# Power_981228.net
KiCad netlist of a schematic drawn in Altium Designer
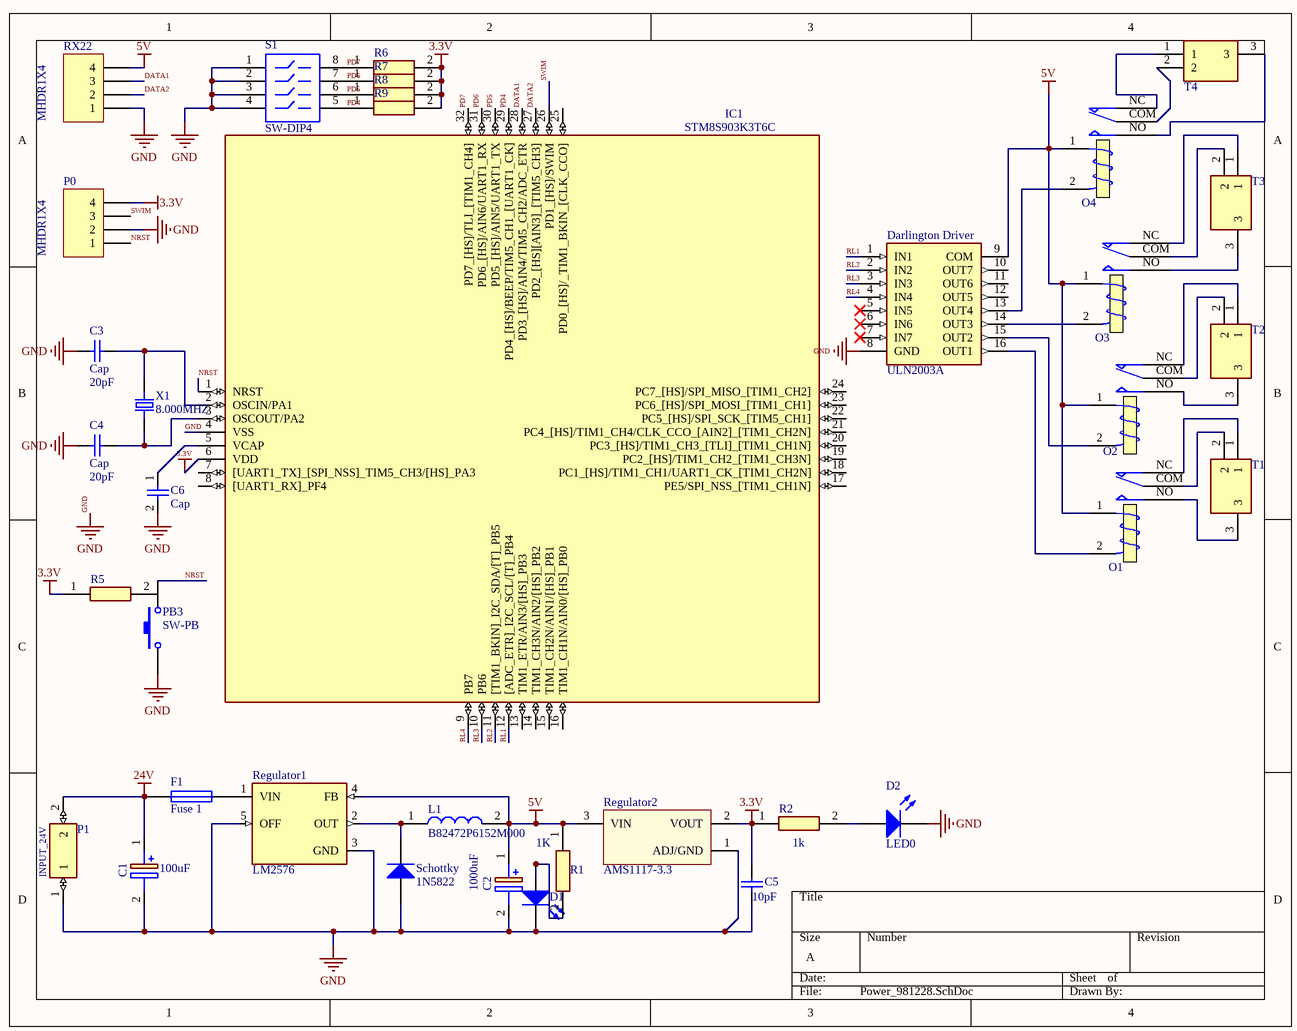
[diagram p0: Power_981228.SchDoc]

(export (version "E")
  (design (tool "Eeschema 10.0.6"))
  (components
    (comp (ref "C1")
      (value "100uF")
      (footprint "SamacSys:CAPPRD550W60D1050H2150")
      (description "Capacitor Polarised")
      (fields (field (name "MANUFACTURER_PART_NUMBER") "108CKE025M"))
      (libsource (lib "*") (part "108CKE025M"))
    )
    (comp (ref "C2")
      (value "1000uF")
      (footprint "SamacSys:CAPPRD550W60D1050H2150")
      (description "Capacitor Polarised")
      (fields (field (name "MANUFACTURER_PART_NUMBER") "108CKE025M"))
      (libsource (lib "*") (part "108CKE025M"))
    )
    (comp (ref "C3")
      (value "Cap")
      (footprint "RAD-0.3")
      (description "Capacitor")
      (fields (field (name "ALTIUM_VALUE") "20pF") (field (name "PUBLISHER") "Altium Limited"))
      (libsource (lib "Miscellaneous Devices") (part "Cap"))
    )
    (comp (ref "C4")
      (value "Cap")
      (footprint "RAD-0.3")
      (description "Capacitor")
      (fields (field (name "ALTIUM_VALUE") "20pF") (field (name "PUBLISHER") "Altium Limited"))
      (libsource (lib "Miscellaneous Devices") (part "Cap"))
    )
    (comp (ref "C5")
      (value "10pF")
      (footprint "RAD-0.3")
      (description "Capacitor")
      (fields (field (name "Comment") "Cap") (field (name "PUBLISHER") "Altium Limited"))
      (libsource (lib "Miscellaneous Devices") (part "Cap"))
    )
    (comp (ref "C6")
      (value "Cap")
      (footprint "RAD-0.3")
      (description "Capacitor")
      (fields (field (name "PUBLISHER") "Altium Limited"))
      (libsource (lib "") (part "Cap_1"))
    )
    (comp (ref "D1")
      (value "LED0")
      (footprint "LED-0")
      (description "Typical INFRARED GaAs LED")
      (fields (field (name "PUBLISHER") "Altium Limited"))
      (libsource (lib "Miscellaneous Devices") (part "LED0"))
    )
    (comp (ref "D2")
      (value "LED0")
      (footprint "LED-0")
      (description "Typical INFRARED GaAs LED")
      (fields (field (name "PUBLISHER") "Altium Limited"))
      (libsource (lib "Miscellaneous Devices") (part "LED0"))
    )
    (comp (ref "Darlington Driver")
      (value "ULN2003A")
      (footprint "SamacSys:DIP794W56P254L1918H533Q16N")
      (description "Integrated Circuit")
      (fields (field (name "MOUSER PART NUMBER") "511-ULN2003A") (field (name "RS PART NUMBER") "6868209"))
      (libsource (lib "*") (part "ULN2003A"))
    )
    (comp (ref "F1")
      (value "Fuse 1")
      (footprint "PIN-W2/E2.8")
      (description "Fuse")
      (fields (field (name "PUBLISHER") "Altium Limited"))
      (libsource (lib "Miscellaneous Devices") (part "Fuse 1"))
    )
    (comp (ref "IC1")
      (value "STM8S903K3T6C")
      (footprint "SamacSys:QFP80P900X900X160-32N")
      (description "Integrated Circuit")
      (fields
        (field (name "MOUSER PART NUMBER") "511-STM8S903K3T6C")
        (field (name "RS PART NUMBER") "7250025P")
      )
      (libsource (lib "*") (part "STM8S903K3T6C"))
    )
    (comp (ref "L1")
      (value "B82472P6152M000")
      (footprint "SamacSys:INDPM7474X450N")
      (description "Inductor")
      (fields (field (name "MOUSER PART NUMBER") "871-B82472P6152M000"))
      (libsource (lib "*") (part "B82472P6152M000"))
    )
    (comp (ref "O1")
      (value "12V SMALL")
      (footprint "Relay_5_Small")
      (fields
        (field (name "MANUFACTURER") "TIANBO")
        (field (name "MANUFACTURE PART #") "HJR-78F-12VDC-S-Z")
        (field (name "MANUFACTURER PART NUMBER") "STM8S003K3T6C")
      )
      (libsource (lib "Relay_Small") (part "HJR-78F-12VDC-S-Z"))
    )
    (comp (ref "O2")
      (value "12V SMALL")
      (footprint "Relay_5_Small")
      (fields (field (name "MANUFACTURER") "TIANBO") (field (name "MANUFACTURE PART #") "HJR-78F-12VDC-S-Z"))
      (libsource (lib "Relay_Small") (part "HJR-78F-12VDC-S-Z"))
    )
    (comp (ref "O3")
      (value "12V SMALL")
      (footprint "Relay_5_Small")
      (fields (field (name "MANUFACTURER") "TIANBO") (field (name "MANUFACTURE PART #") "HJR-78F-12VDC-S-Z"))
      (libsource (lib "Relay_Small") (part "HJR-78F-12VDC-S-Z"))
    )
    (comp (ref "O4")
      (value "12V SMALL")
      (footprint "Relay_5_Small")
      (fields (field (name "MANUFACTURER") "TIANBO") (field (name "MANUFACTURE PART #") "HJR-78F-12VDC-S-Z"))
      (libsource (lib "Relay_Small") (part "HJR-78F-12VDC-S-Z"))
    )
    (comp (ref "P0")
      (value "MHDR1X4")
      (footprint "MHDR1X4")
      (description "Header, 4-Pin")
      (fields (field (name "PUBLISHER") "Altium Limited"))
      (libsource (lib "Miscellaneous Connectors") (part "MHDR1X4"))
    )
    (comp (ref "P1")
      (value "INPUT_24V")
      (footprint "SamacSys:1725656")
      (description "Connector")
      (fields
        (field (name "MANUFACTURER_PART_NUMBER") "1725656")
        (field (name "MOUSER PART NUMBER") "651-1725656")
      )
      (libsource (lib "*") (part "1725656"))
    )
    (comp (ref "PB3")
      (value "SW-PB")
      (footprint "SPST-2")
      (description "Switch")
      (fields (field (name "PUBLISHER") "Altium Limited"))
      (libsource (lib "Miscellaneous Devices") (part "SW-PB"))
    )
    (comp (ref "R1")
      (value "1K")
      (footprint "SamacSys:RESC3216X60N")
      (description "Resistor")
      (fields
        (field (name "MANUFACTURER_PART_NUMBER") "CRCW120610M0FKEA")
        (field (name "MOUSER PART NUMBER") "71-CRCW1206-10M-E3")
      )
      (libsource (lib "") (part "CRCW120610M0FKEA_1"))
    )
    (comp (ref "R2")
      (value "1k")
      (footprint "SamacSys:RESC3216X60N")
      (description "Resistor")
      (fields
        (field (name "MANUFACTURER_PART_NUMBER") "CRCW120610M0FKEA")
        (field (name "MOUSER PART NUMBER") "71-CRCW1206-10M-E3")
      )
      (libsource (lib "*") (part "CRCW120610M0FKEA"))
    )
    (comp (ref "R5")
      (value "CRCW120610M0FKEA")
      (footprint "SamacSys:RESC3216X60N")
      (description "Resistor")
      (fields (field (name "MOUSER PART NUMBER") "71-CRCW1206-10M-E3"))
      (libsource (lib "*") (part "CRCW120610M0FKEA"))
    )
    (comp (ref "R6")
      (value "CRCW120610M0FKEA")
      (footprint "SamacSys:RESC3216X60N")
      (description "Resistor")
      (fields (field (name "MOUSER PART NUMBER") "71-CRCW1206-10M-E3"))
      (libsource (lib "*") (part "CRCW120610M0FKEA"))
    )
    (comp (ref "R7")
      (value "CRCW120610M0FKEA")
      (footprint "SamacSys:RESC3216X60N")
      (description "Resistor")
      (fields (field (name "MOUSER PART NUMBER") "71-CRCW1206-10M-E3"))
      (libsource (lib "*") (part "CRCW120610M0FKEA"))
    )
    (comp (ref "R8")
      (value "CRCW120610M0FKEA")
      (footprint "SamacSys:RESC3216X60N")
      (description "Resistor")
      (fields (field (name "MOUSER PART NUMBER") "71-CRCW1206-10M-E3"))
      (libsource (lib "*") (part "CRCW120610M0FKEA"))
    )
    (comp (ref "R9")
      (value "CRCW120610M0FKEA")
      (footprint "SamacSys:RESC3216X60N")
      (description "Resistor")
      (fields (field (name "MOUSER PART NUMBER") "71-CRCW1206-10M-E3"))
      (libsource (lib "*") (part "CRCW120610M0FKEA"))
    )
    (comp (ref "Regulator1")
      (value "LM2576")
      (footprint "TO220-5")
      (fields (field (name "MF") "Texas Instruments"))
      (libsource (lib "LM2576") (part "LM2576"))
    )
    (comp (ref "Regulator2")
      (value "AMS1117-3.3")
      (footprint "SOT229P700X180-4N")
      (description "Low-dropout regulator")
      (libsource (lib "IC_Library") (part "AMS1117"))
    )
    (comp (ref "RX22")
      (value "MHDR1X4")
      (footprint "MHDR1X4")
      (description "Header, 4-Pin")
      (fields (field (name "PUBLISHER") "Altium Limited"))
      (libsource (lib "Miscellaneous Connectors") (part "MHDR1X4"))
    )
    (comp (ref "S1")
      (value "SW-DIP4")
      (footprint "DIP-8")
      (description "DIP Switch")
      (fields (field (name "PUBLISHER") "Altium Limited"))
      (libsource (lib "Miscellaneous Devices") (part "SW-DIP4"))
    )
    (comp (ref "Schottky")
      (value "1N5822")
      (footprint "DO-41")
      (description "1 Amp General Purpose Rectifier")
      (fields (field (name "PUBLISHER") "Altium Limited"))
      (libsource (lib "Miscellaneous Devices") (part "Diode 1N4001"))
    )
    (comp (ref "T1")
      (value "1725669")
      (footprint "SamacSys:1725669")
      (description "Connector")
      (fields (field (name "MOUSER PART NUMBER") "651-1725669") (field (name "RS PART NUMBER") "3909039"))
      (libsource (lib "*") (part "1725669"))
    )
    (comp (ref "T2")
      (value "1725669")
      (footprint "SamacSys:1725669")
      (description "Connector")
      (fields (field (name "MOUSER PART NUMBER") "651-1725669") (field (name "RS PART NUMBER") "3909039"))
      (libsource (lib "*") (part "1725669"))
    )
    (comp (ref "T3")
      (value "1725669")
      (footprint "SamacSys:1725669")
      (description "Connector")
      (fields (field (name "MOUSER PART NUMBER") "651-1725669") (field (name "RS PART NUMBER") "3909039"))
      (libsource (lib "*") (part "1725669"))
    )
    (comp (ref "T4")
      (value "1725669")
      (footprint "SamacSys:1725669")
      (description "Connector")
      (fields (field (name "MOUSER PART NUMBER") "651-1725669") (field (name "RS PART NUMBER") "3909039"))
      (libsource (lib "") (part "1725669_1"))
    )
    (comp (ref "X1")
      (value "8.000MHZ")
      (footprint "XTAL_ABLS-8.000MHZ-B2-T")
      (description "8MHz Â±20ppm Crystal 18pF 80 Ohms HC-49/US")
      (fields (field (name "MP") "ABLS-8.000MHZ-B2") (field (name "MF") "Abracon LLC"))
      (libsource (lib "ABLS-8.000MHZ-B2-T") (part "ABLS-8.000MHZ-B2-T"))
    )
  )
  (nets
    (net (code "1") (name "/DATA1") (class "Default")
      (node (ref "IC1") (pin "28") (pinfunction "PD3_[HS]/AIN4/TIM5_CH2/ADC_ETR_28") (pintype "bidirectional"))
      (node (ref "RX22") (pin "3") (pinfunction "3_3") (pintype "passive"))
    )
    (net (code "2") (name "/DATA2") (class "Default")
      (node (ref "IC1") (pin "27") (pinfunction "PD2_[HS][AIN3]_[TIM5_CH3]_27") (pintype "bidirectional"))
      (node (ref "RX22") (pin "2") (pinfunction "2_2") (pintype "passive"))
    )
    (net (code "3") (name "/NRST") (class "Default")
      (node (ref "IC1") (pin "1") (pinfunction "NRST_1") (pintype "bidirectional"))
      (node (ref "P0") (pin "1") (pinfunction "1_1") (pintype "passive"))
      (node (ref "PB3") (pin "2") (pinfunction "2_2") (pintype "passive"))
    )
    (net (code "4") (name "/PD4") (class "Default")
      (node (ref "IC1") (pin "29") (pinfunction "PD4_[HS]/BEEP/TIM5_CH1_[UART1_CK]_29") (pintype "bidirectional"))
      (node (ref "R9") (pin "1") (pinfunction "1_1") (pintype "passive"))
      (node (ref "S1") (pin "5") (pinfunction "5_5") (pintype "passive"))
    )
    (net (code "5") (name "/PD5") (class "Default")
      (node (ref "IC1") (pin "30") (pinfunction "PD5_[HS]/AIN5/UART1_TX_30") (pintype "bidirectional"))
      (node (ref "R8") (pin "1") (pinfunction "1_1") (pintype "passive"))
      (node (ref "S1") (pin "6") (pinfunction "6_6") (pintype "passive"))
    )
    (net (code "6") (name "/PD6") (class "Default")
      (node (ref "IC1") (pin "31") (pinfunction "PD6_[HS]/AIN6/UART1_RX_31") (pintype "bidirectional"))
      (node (ref "R7") (pin "1") (pinfunction "1_1") (pintype "passive"))
      (node (ref "S1") (pin "7") (pinfunction "7_7") (pintype "passive"))
    )
    (net (code "7") (name "/PD7") (class "Default")
      (node (ref "IC1") (pin "32") (pinfunction "PD7_[HS]/TLI_[TIM1_CH4]_32") (pintype "bidirectional"))
      (node (ref "R6") (pin "1") (pinfunction "1_1") (pintype "passive"))
      (node (ref "S1") (pin "8") (pinfunction "8_8") (pintype "passive"))
    )
    (net (code "8") (name "/RL1") (class "Default")
      (node (ref "Darlington Driver") (pin "1") (pinfunction "IN1_1") (pintype "input"))
      (node (ref "IC1") (pin "12") (pinfunction "[ADC_ETR]_I2C_SCL/[T]_PB4_12") (pintype "bidirectional"))
    )
    (net (code "9") (name "/RL2") (class "Default")
      (node (ref "Darlington Driver") (pin "2") (pinfunction "IN2_2") (pintype "input"))
      (node (ref "IC1") (pin "11") (pinfunction "[TIM1_BKIN]_I2C_SDA/[T]_PB5_11") (pintype "bidirectional"))
    )
    (net (code "10") (name "/RL3") (class "Default")
      (node (ref "Darlington Driver") (pin "3") (pinfunction "IN3_3") (pintype "input"))
      (node (ref "IC1") (pin "10") (pinfunction "PB6_10") (pintype "bidirectional"))
    )
    (net (code "11") (name "/RL4") (class "Default")
      (node (ref "Darlington Driver") (pin "4") (pinfunction "IN4_4") (pintype "input"))
      (node (ref "IC1") (pin "9") (pinfunction "PB7_9") (pintype "bidirectional"))
    )
    (net (code "12") (name "/SWIM") (class "Default")
      (node (ref "IC1") (pin "26") (pinfunction "PD1_[HS]/SWIM_26") (pintype "bidirectional"))
      (node (ref "P0") (pin "3") (pinfunction "3_3") (pintype "passive"))
    )
    (net (code "13") (name "3.3V") (class "Default")
      (node (ref "C5") (pin "1") (pinfunction "1_1") (pintype "passive"))
      (node (ref "IC1") (pin "6") (pinfunction "VDD_6") (pintype "power_in"))
      (node (ref "P0") (pin "4") (pinfunction "4_4") (pintype "passive"))
      (node (ref "R2") (pin "1") (pinfunction "1_1") (pintype "passive"))
      (node (ref "R5") (pin "1") (pinfunction "1_1") (pintype "passive"))
      (node (ref "R6") (pin "2") (pinfunction "2_2") (pintype "passive"))
      (node (ref "R7") (pin "2") (pinfunction "2_2") (pintype "passive"))
      (node (ref "R8") (pin "2") (pinfunction "2_2") (pintype "passive"))
      (node (ref "R9") (pin "2") (pinfunction "2_2") (pintype "passive"))
      (node (ref "Regulator2") (pin "2") (pinfunction "VOUT_2") (pintype "power_in"))
    )
    (net (code "14") (name "5V") (class "Default")
      (node (ref "C2") (pin "1") (pinfunction "+_1") (pintype "passive"))
      (node (ref "Darlington Driver") (pin "9") (pinfunction "COM_9") (pintype "passive"))
      (node (ref "L1") (pin "2") (pinfunction "2_2") (pintype "passive"))
      (node (ref "O1") (pin "1") (pinfunction "1_1") (pintype "passive"))
      (node (ref "O2") (pin "1") (pinfunction "1_1") (pintype "passive"))
      (node (ref "O3") (pin "1") (pinfunction "1_1") (pintype "passive"))
      (node (ref "O4") (pin "1") (pinfunction "1_1") (pintype "passive"))
      (node (ref "R1") (pin "1") (pinfunction "1_1") (pintype "passive"))
      (node (ref "RX22") (pin "4") (pinfunction "4_4") (pintype "passive"))
      (node (ref "Regulator1") (pin "4") (pinfunction "FB_4") (pintype "input"))
      (node (ref "Regulator2") (pin "3") (pinfunction "VIN_3") (pintype "power_in"))
    )
    (net (code "15") (name "24V") (class "Default")
      (node (ref "C1") (pin "1") (pinfunction "+_1") (pintype "passive"))
      (node (ref "F1") (pin "1") (pinfunction "1_1") (pintype "passive"))
      (node (ref "P1") (pin "2") (pinfunction "2_2") (pintype "bidirectional"))
    )
    (net (code "16") (name "GND") (class "Default")
      (node (ref "C1") (pin "2") (pinfunction "-_2") (pintype "passive"))
      (node (ref "C2") (pin "2") (pinfunction "-_2") (pintype "passive"))
      (node (ref "C3") (pin "1") (pinfunction "1_1") (pintype "passive"))
      (node (ref "C4") (pin "1") (pinfunction "1_1") (pintype "passive"))
      (node (ref "C5") (pin "2") (pinfunction "2_2") (pintype "passive"))
      (node (ref "C6") (pin "2") (pinfunction "2_2") (pintype "passive"))
      (node (ref "D1") (pin "2") (pinfunction "K_2") (pintype "passive"))
      (node (ref "D2") (pin "2") (pinfunction "K_2") (pintype "passive"))
      (node (ref "Darlington Driver") (pin "8") (pinfunction "GND_8") (pintype "power_in"))
      (node (ref "IC1") (pin "4") (pinfunction "VSS_4") (pintype "power_in"))
      (node (ref "P0") (pin "2") (pinfunction "2_2") (pintype "passive"))
      (node (ref "P1") (pin "1") (pinfunction "1_1") (pintype "bidirectional"))
      (node (ref "PB3") (pin "1") (pinfunction "1_1") (pintype "passive"))
      (node (ref "RX22") (pin "1") (pinfunction "1_1") (pintype "passive"))
      (node (ref "Regulator1") (pin "3") (pinfunction "GND_3") (pintype "power_in"))
      (node (ref "Regulator1") (pin "5") (pinfunction "OFF_5") (pintype "input"))
      (node (ref "Regulator2") (pin "1") (pinfunction "ADJ/GND_1") (pintype "power_in"))
      (node (ref "S1") (pin "1") (pinfunction "1_1") (pintype "passive"))
      (node (ref "S1") (pin "2") (pinfunction "2_2") (pintype "passive"))
      (node (ref "S1") (pin "3") (pinfunction "3_3") (pintype "passive"))
      (node (ref "S1") (pin "4") (pinfunction "4_4") (pintype "passive"))
      (node (ref "Schottky") (pin "1") (pinfunction "A_1") (pintype "passive"))
    )
    (net (code "17") (name "Net-(D1-A)") (class "Default")
      (node (ref "D1") (pin "1") (pinfunction "A_1") (pintype "passive"))
      (node (ref "R1") (pin "2") (pinfunction "2_2") (pintype "passive"))
    )
    (net (code "18") (name "Net-(D2-A)") (class "Default")
      (node (ref "D2") (pin "1") (pinfunction "A_1") (pintype "passive"))
      (node (ref "R2") (pin "2") (pinfunction "2_2") (pintype "passive"))
    )
    (net (code "19") (name "Net-(Darlington Driver-OUT1)") (class "Default")
      (node (ref "Darlington Driver") (pin "16") (pinfunction "OUT1_16") (pintype "output"))
      (node (ref "O1") (pin "2") (pinfunction "2_2") (pintype "passive"))
    )
    (net (code "20") (name "Net-(Darlington Driver-OUT2)") (class "Default")
      (node (ref "Darlington Driver") (pin "15") (pinfunction "OUT2_15") (pintype "output"))
      (node (ref "O2") (pin "2") (pinfunction "2_2") (pintype "passive"))
    )
    (net (code "21") (name "Net-(Darlington Driver-OUT3)") (class "Default")
      (node (ref "Darlington Driver") (pin "14") (pinfunction "OUT3_14") (pintype "output"))
      (node (ref "O3") (pin "2") (pinfunction "2_2") (pintype "passive"))
    )
    (net (code "22") (name "Net-(Darlington Driver-OUT4)") (class "Default")
      (node (ref "Darlington Driver") (pin "13") (pinfunction "OUT4_13") (pintype "output"))
      (node (ref "O4") (pin "2") (pinfunction "2_2") (pintype "passive"))
    )
    (net (code "23") (name "Net-(IC1-OSCIN{slash}PA1)") (class "Default")
      (node (ref "C3") (pin "2") (pinfunction "2_2") (pintype "passive"))
      (node (ref "IC1") (pin "2") (pinfunction "OSCIN/PA1_2") (pintype "bidirectional"))
      (node (ref "X1") (pin "2") (pinfunction "2_2") (pintype "passive"))
    )
    (net (code "24") (name "Net-(IC1-OSCOUT{slash}PA2)") (class "Default")
      (node (ref "C4") (pin "2") (pinfunction "2_2") (pintype "passive"))
      (node (ref "IC1") (pin "3") (pinfunction "OSCOUT/PA2_3") (pintype "bidirectional"))
      (node (ref "X1") (pin "1") (pinfunction "1_1") (pintype "passive"))
    )
    (net (code "25") (name "Net-(IC1-VCAP)") (class "Default")
      (node (ref "C6") (pin "1") (pinfunction "1_1") (pintype "passive"))
      (node (ref "IC1") (pin "5") (pinfunction "VCAP_5") (pintype "power_in"))
    )
    (net (code "26") (name "Net-(O1-PadCOM)") (class "Default")
      (node (ref "O1") (pin "COM") (pinfunction "COM_COM") (pintype "passive"))
      (node (ref "T1") (pin "2") (pinfunction "2_2") (pintype "passive"))
    )
    (net (code "27") (name "Net-(O1-PadNC)") (class "Default")
      (node (ref "O1") (pin "NC") (pinfunction "NC_NC") (pintype "passive"))
      (node (ref "T1") (pin "1") (pinfunction "1_1") (pintype "passive"))
    )
    (net (code "28") (name "Net-(O1-PadNO)") (class "Default")
      (node (ref "O1") (pin "NO") (pinfunction "NO_NO") (pintype "passive"))
      (node (ref "T1") (pin "3") (pinfunction "3_3") (pintype "passive"))
    )
    (net (code "29") (name "Net-(O2-PadCOM)") (class "Default")
      (node (ref "O2") (pin "COM") (pinfunction "COM_COM") (pintype "passive"))
      (node (ref "T2") (pin "2") (pinfunction "2_2") (pintype "passive"))
    )
    (net (code "30") (name "Net-(O2-PadNC)") (class "Default")
      (node (ref "O2") (pin "NC") (pinfunction "NC_NC") (pintype "passive"))
      (node (ref "T2") (pin "1") (pinfunction "1_1") (pintype "passive"))
    )
    (net (code "31") (name "Net-(O2-PadNO)") (class "Default")
      (node (ref "O2") (pin "NO") (pinfunction "NO_NO") (pintype "passive"))
      (node (ref "T2") (pin "3") (pinfunction "3_3") (pintype "passive"))
    )
    (net (code "32") (name "Net-(O3-PadCOM)") (class "Default")
      (node (ref "O3") (pin "COM") (pinfunction "COM_COM") (pintype "passive"))
      (node (ref "T3") (pin "2") (pinfunction "2_2") (pintype "passive"))
    )
    (net (code "33") (name "Net-(O3-PadNC)") (class "Default")
      (node (ref "O3") (pin "NC") (pinfunction "NC_NC") (pintype "passive"))
      (node (ref "T3") (pin "1") (pinfunction "1_1") (pintype "passive"))
    )
    (net (code "34") (name "Net-(O3-PadNO)") (class "Default")
      (node (ref "O3") (pin "NO") (pinfunction "NO_NO") (pintype "passive"))
      (node (ref "T3") (pin "3") (pinfunction "3_3") (pintype "passive"))
    )
    (net (code "35") (name "Net-(O4-PadCOM)") (class "Default")
      (node (ref "O4") (pin "COM") (pinfunction "COM_COM") (pintype "passive"))
      (node (ref "T4") (pin "2") (pinfunction "2_2") (pintype "passive"))
    )
    (net (code "36") (name "Net-(O4-PadNC)") (class "Default")
      (node (ref "O4") (pin "NC") (pinfunction "NC_NC") (pintype "passive"))
      (node (ref "T4") (pin "1") (pinfunction "1_1") (pintype "passive"))
    )
    (net (code "37") (name "Net-(O4-PadNO)") (class "Default")
      (node (ref "O4") (pin "NO") (pinfunction "NO_NO") (pintype "passive"))
      (node (ref "T4") (pin "3") (pinfunction "3_3") (pintype "passive"))
    )
    (net (code "38") (name "Net-(Regulator1-OUT)") (class "Default")
      (node (ref "L1") (pin "1") (pinfunction "1_1") (pintype "passive"))
      (node (ref "Regulator1") (pin "2") (pinfunction "OUT_2") (pintype "output"))
      (node (ref "Schottky") (pin "2") (pinfunction "K_2") (pintype "passive"))
    )
    (net (code "39") (name "Net-(Regulator1-VIN)") (class "Default")
      (node (ref "F1") (pin "2") (pinfunction "2_2") (pintype "passive"))
      (node (ref "Regulator1") (pin "1") (pinfunction "VIN_1") (pintype "power_in"))
    )
    (net (code "40") (name "unconnected-(Darlington Driver-IN5-Pad5)") (class "Default")
      (node (ref "Darlington Driver") (pin "5") (pinfunction "IN5_5") (pintype "input+no_connect"))
    )
    (net (code "41") (name "unconnected-(Darlington Driver-IN6-Pad6)") (class "Default")
      (node (ref "Darlington Driver") (pin "6") (pinfunction "IN6_6") (pintype "input+no_connect"))
    )
    (net (code "42") (name "unconnected-(Darlington Driver-IN7-Pad7)") (class "Default")
      (node (ref "Darlington Driver") (pin "7") (pinfunction "IN7_7") (pintype "input+no_connect"))
    )
    (net (code "43") (name "unconnected-(Darlington Driver-OUT5-Pad12)") (class "Default")
      (node (ref "Darlington Driver") (pin "12") (pinfunction "OUT5_12") (pintype "output"))
    )
    (net (code "44") (name "unconnected-(Darlington Driver-OUT6-Pad11)") (class "Default")
      (node (ref "Darlington Driver") (pin "11") (pinfunction "OUT6_11") (pintype "output"))
    )
    (net (code "45") (name "unconnected-(Darlington Driver-OUT7-Pad10)") (class "Default")
      (node (ref "Darlington Driver") (pin "10") (pinfunction "OUT7_10") (pintype "output"))
    )
    (net (code "46") (name "unconnected-(IC1-PC1_[HS]{slash}TIM1_CH1{slash}UART1_CK_[TIM1_CH2N]-Pad18)") (class "Default")
      (node (ref "IC1") (pin "18") (pinfunction "PC1_[HS]/TIM1_CH1/UART1_CK_[TIM1_CH2N]_18") (pintype "bidirectional"))
    )
    (net (code "47") (name "unconnected-(IC1-PC2_[HS]{slash}TIM1_CH2_[TIM1_CH3N]-Pad19)") (class "Default")
      (node (ref "IC1") (pin "19") (pinfunction "PC2_[HS]/TIM1_CH2_[TIM1_CH3N]_19") (pintype "bidirectional"))
    )
    (net (code "48") (name "unconnected-(IC1-PC3_[HS]{slash}TIM1_CH3_[TLI]_[TIM1_CH1N]-Pad20)") (class "Default")
      (node (ref "IC1") (pin "20") (pinfunction "PC3_[HS]/TIM1_CH3_[TLI]_[TIM1_CH1N]_20") (pintype "bidirectional"))
    )
    (net (code "49") (name "unconnected-(IC1-PC4_[HS]{slash}TIM1_CH4{slash}CLK_CCO_[AIN2]_[TIM1_CH2N]-Pad21)") (class "Default")
      (node (ref "IC1") (pin "21") (pinfunction "PC4_[HS]/TIM1_CH4/CLK_CCO_[AIN2]_[TIM1_CH2N]_21") (pintype "bidirectional"))
    )
    (net (code "50") (name "unconnected-(IC1-PC5_[HS]{slash}SPI_SCK_[TIM5_CH1]-Pad22)") (class "Default")
      (node (ref "IC1") (pin "22") (pinfunction "PC5_[HS]/SPI_SCK_[TIM5_CH1]_22") (pintype "bidirectional"))
    )
    (net (code "51") (name "unconnected-(IC1-PC6_[HS]{slash}SPI_MOSI_[TIM1_CH1]-Pad23)") (class "Default")
      (node (ref "IC1") (pin "23") (pinfunction "PC6_[HS]/SPI_MOSI_[TIM1_CH1]_23") (pintype "bidirectional"))
    )
    (net (code "52") (name "unconnected-(IC1-PC7_[HS]{slash}SPI_MISO_[TIM1_CH2]-Pad24)") (class "Default")
      (node (ref "IC1") (pin "24") (pinfunction "PC7_[HS]/SPI_MISO_[TIM1_CH2]_24") (pintype "bidirectional"))
    )
    (net (code "53") (name "unconnected-(IC1-PD0_[HS]{slash}_TIM1_BKIN_[CLK_CCO]-Pad25)") (class "Default")
      (node (ref "IC1") (pin "25") (pinfunction "PD0_[HS]/_TIM1_BKIN_[CLK_CCO]_25") (pintype "bidirectional"))
    )
    (net (code "54") (name "unconnected-(IC1-PE5{slash}SPI_NSS_[TIM1_CH1N]-Pad17)") (class "Default")
      (node (ref "IC1") (pin "17") (pinfunction "PE5/SPI_NSS_[TIM1_CH1N]_17") (pintype "bidirectional"))
    )
    (net (code "55") (name "unconnected-(IC1-TIM1_CH1N{slash}AIN0{slash}[HS]_PB0-Pad16)") (class "Default")
      (node (ref "IC1") (pin "16") (pinfunction "TIM1_CH1N/AIN0/[HS]_PB0_16") (pintype "bidirectional"))
    )
    (net (code "56") (name "unconnected-(IC1-TIM1_CH2N{slash}AIN1{slash}[HS]_PB1-Pad15)") (class "Default")
      (node (ref "IC1") (pin "15") (pinfunction "TIM1_CH2N/AIN1/[HS]_PB1_15") (pintype "bidirectional"))
    )
    (net (code "57") (name "unconnected-(IC1-TIM1_CH3N{slash}AIN2{slash}[HS]_PB2-Pad14)") (class "Default")
      (node (ref "IC1") (pin "14") (pinfunction "TIM1_CH3N/AIN2/[HS]_PB2_14") (pintype "bidirectional"))
    )
    (net (code "58") (name "unconnected-(IC1-TIM1_ETR{slash}AIN3{slash}[HS]_PB3-Pad13)") (class "Default")
      (node (ref "IC1") (pin "13") (pinfunction "TIM1_ETR/AIN3/[HS]_PB3_13") (pintype "bidirectional"))
    )
    (net (code "59") (name "unconnected-(IC1-[UART1_RX]_PF4-Pad8)") (class "Default")
      (node (ref "IC1") (pin "8") (pinfunction "[UART1_RX]_PF4_8") (pintype "bidirectional"))
    )
    (net (code "60") (name "unconnected-(IC1-[UART1_TX]_[SPI_NSS]_TIM5_CH3{slash}[HS]_PA3-Pad7)") (class "Default")
      (node (ref "IC1") (pin "7") (pinfunction "[UART1_TX]_[SPI_NSS]_TIM5_CH3/[HS]_PA3_7") (pintype "bidirectional"))
    )
    (net (code "61") (name "unconnected-(R5-Pad2)") (class "Default")
      (node (ref "R5") (pin "2") (pinfunction "2_2") (pintype "passive"))
    )
  )
)
